# SEM_V1.net
KiCad netlist of a schematic drawn in EAGLE
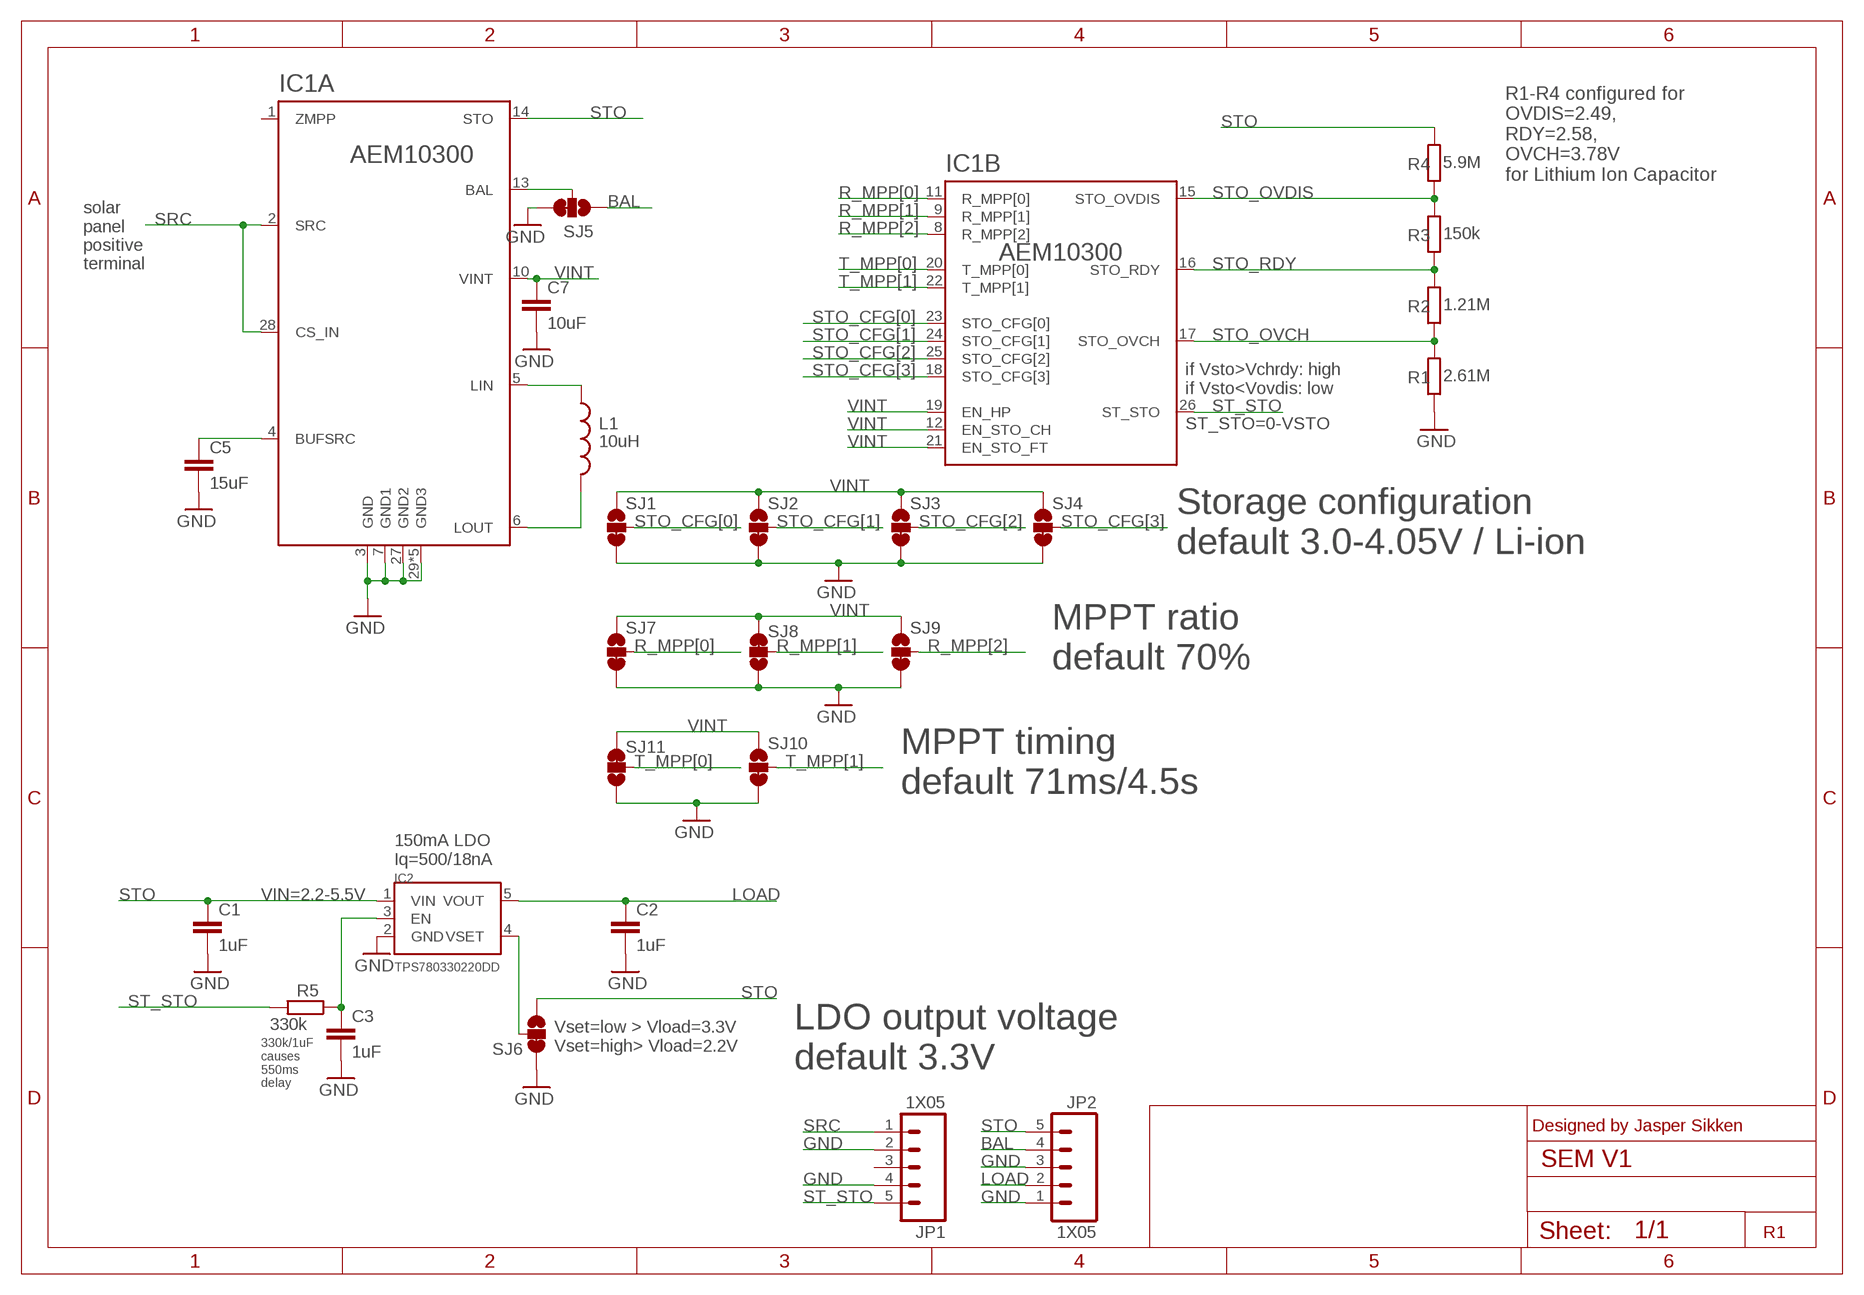
[diagram p0: schematic, sheet 1]

(export (version "E")
  (design (tool "Eeschema 10.0.6"))
  (components
    (comp (ref "C1")
      (value "1uF")
      (footprint "eagle-import:C0402")
      (libsource (lib "eagle-import") (part "C0402_1UF"))
    )
    (comp (ref "C2")
      (value "1uF")
      (footprint "eagle-import:C0402")
      (libsource (lib "eagle-import") (part "C0402_1UF"))
    )
    (comp (ref "C3")
      (value "1uF")
      (footprint "eagle-import:C0402")
      (libsource (lib "eagle-import") (part "C_0402"))
    )
    (comp (ref "C5")
      (value "15uF")
      (footprint "eagle-import:C0402")
      (libsource (lib "eagle-import") (part "C_0402"))
    )
    (comp (ref "C7")
      (value "10uF")
      (footprint "eagle-import:C0402")
      (libsource (lib "eagle-import") (part "C_0402"))
    )
    (comp (ref "IC1")
      (value "AEM10300")
      (footprint "eagle-import:QFN28P4X4")
      (libsource (lib "eagle-import") (part "AEM10300"))
    )
    (comp (ref "IC2")
      (value "TPS780330220DD")
      (footprint "eagle-import:SOT23-5")
      (libsource (lib "eagle-import") (part "TPS780330220DD"))
    )
    (comp (ref "JP1")
      (value "1X05")
      (footprint "eagle-import:1X05_2.54MM_ROUND_NOSILK")
      (libsource (lib "eagle-import") (part "1X05"))
    )
    (comp (ref "JP2")
      (value "1X05")
      (footprint "eagle-import:1X05_2.54MM_ROUND_NOSILK")
      (libsource (lib "eagle-import") (part "1X05"))
    )
    (comp (ref "L1")
      (value "10uH")
      (footprint "eagle-import:L_1008_[2520]")
      (fields (field (name "MF") "MURATA") (field (name "MPN") "DFE252010F-100"))
      (libsource (lib "eagle-import") (part "L"))
    )
    (comp (ref "R1")
      (value "2.61M")
      (footprint "eagle-import:R0402")
      (fields (field (name "MF") "Walsin") (field (name "MPN") "WR04X1004FTL"))
      (libsource (lib "eagle-import") (part "R0402_1M"))
    )
    (comp (ref "R2")
      (value "1.21M")
      (footprint "eagle-import:R0402")
      (fields (field (name "MF") "Walsin") (field (name "MPN") "WR04X1004FTL"))
      (libsource (lib "eagle-import") (part "R0402_1M"))
    )
    (comp (ref "R3")
      (value "150k")
      (footprint "eagle-import:R0402")
      (fields (field (name "MF") "Walsin") (field (name "MPN") "WR04X1004FTL"))
      (libsource (lib "eagle-import") (part "R0402_1M"))
    )
    (comp (ref "R4")
      (value "5.9M")
      (footprint "eagle-import:R0402")
      (fields (field (name "MF") "Walsin") (field (name "MPN") "WR04X1004FTL"))
      (libsource (lib "eagle-import") (part "R0402_1M"))
    )
    (comp (ref "R5")
      (value "330k")
      (footprint "eagle-import:R0402")
      (fields (field (name "MF") "Walsin") (field (name "MPN") "WR04X1004FTL"))
      (libsource (lib "eagle-import") (part "R0402_1M"))
    )
    (comp (ref "SJ1")
      (value "SOLDERJUMPER_3WAY_12SHORT3WAY")
      (footprint "eagle-import:SJ_3S_NC_0402")
      (libsource (lib "eagle-import") (part "SOLDERJUMPER_3WAY_12SHORT3WAY"))
    )
    (comp (ref "SJ2")
      (value "SOLDERJUMPER_3WAY_12SHORT3WAY")
      (footprint "eagle-import:SJ_3S_NC_0402")
      (libsource (lib "eagle-import") (part "SOLDERJUMPER_3WAY_12SHORT3WAY"))
    )
    (comp (ref "SJ3")
      (value "SOLDERJUMPER_3WAY_12SHORT3WAY")
      (footprint "eagle-import:SJ_3S_NC_0402")
      (libsource (lib "eagle-import") (part "SOLDERJUMPER_3WAY_12SHORT3WAY"))
    )
    (comp (ref "SJ4")
      (value "SOLDERJUMPER_3WAY_12SHORT3WAY")
      (footprint "eagle-import:SJ_3S_NC_0402")
      (libsource (lib "eagle-import") (part "SOLDERJUMPER_3WAY_12SHORT3WAY"))
    )
    (comp (ref "SJ5")
      (value "SOLDERJUMPER_3WAY_12SHORT3WAY")
      (footprint "eagle-import:SJ_3S_NC_0402")
      (libsource (lib "eagle-import") (part "SOLDERJUMPER_3WAY_12SHORT3WAY"))
    )
    (comp (ref "SJ6")
      (value "SOLDERJUMPER_3WAY_12SHORT3WAY")
      (footprint "eagle-import:SJ_3S_NC_0402")
      (libsource (lib "eagle-import") (part "SOLDERJUMPER_3WAY_12SHORT3WAY"))
    )
    (comp (ref "SJ7")
      (value "SOLDERJUMPER_3WAY_12SHORT3WAY")
      (footprint "eagle-import:SJ_3S_NC_0402")
      (libsource (lib "eagle-import") (part "SOLDERJUMPER_3WAY_12SHORT3WAY"))
    )
    (comp (ref "SJ8")
      (value "SOLDERJUMPER_3WAY_12SHORT3WAY")
      (footprint "eagle-import:SJ_3S_NC_0402")
      (libsource (lib "eagle-import") (part "SOLDERJUMPER_3WAY_12SHORT3WAY"))
    )
    (comp (ref "SJ9")
      (value "SOLDERJUMPER_3WAY_12SHORT3WAY")
      (footprint "eagle-import:SJ_3S_NC_0402")
      (libsource (lib "eagle-import") (part "SOLDERJUMPER_3WAY_12SHORT3WAY"))
    )
    (comp (ref "SJ10")
      (value "SOLDERJUMPER_3WAY_12SHORT3WAY")
      (footprint "eagle-import:SJ_3S_NC_0402")
      (libsource (lib "eagle-import") (part "SOLDERJUMPER_3WAY_12SHORT3WAY"))
    )
    (comp (ref "SJ11")
      (value "SOLDERJUMPER_3WAY_12SHORT3WAY")
      (footprint "eagle-import:SJ_3S_NC_0402")
      (libsource (lib "eagle-import") (part "SOLDERJUMPER_3WAY_12SHORT3WAY"))
    )
  )
  (nets
    (net (code "1") (name "/BAL") (class "Default")
      (node (ref "JP2") (pin "4") (pinfunction "4_4") (pintype "passive"))
      (node (ref "SJ5") (pin "3") (pinfunction "3_3") (pintype "bidirectional"))
    )
    (net (code "2") (name "/LOAD") (class "Default")
      (node (ref "C2") (pin "1") (pinfunction "1_1") (pintype "passive"))
      (node (ref "IC2") (pin "5") (pinfunction "VOUT_5") (pintype "bidirectional"))
      (node (ref "JP2") (pin "2") (pinfunction "2_2") (pintype "passive"))
    )
    (net (code "3") (name "/R_MPP[0]") (class "Default")
      (node (ref "IC1") (pin "11") (pinfunction "R_MPP[0]_11") (pintype "bidirectional"))
      (node (ref "SJ7") (pin "2") (pinfunction "2_2") (pintype "bidirectional"))
    )
    (net (code "4") (name "/R_MPP[1]") (class "Default")
      (node (ref "IC1") (pin "9") (pinfunction "R_MPP[1]_9") (pintype "bidirectional"))
      (node (ref "SJ8") (pin "2") (pinfunction "2_2") (pintype "bidirectional"))
    )
    (net (code "5") (name "/R_MPP[2]") (class "Default")
      (node (ref "IC1") (pin "8") (pinfunction "R_MPP[2]_8") (pintype "bidirectional"))
      (node (ref "SJ9") (pin "2") (pinfunction "2_2") (pintype "bidirectional"))
    )
    (net (code "6") (name "/SRC") (class "Default")
      (node (ref "IC1") (pin "2") (pinfunction "SRC_2") (pintype "bidirectional"))
      (node (ref "IC1") (pin "28") (pinfunction "CS_IN_28") (pintype "bidirectional"))
      (node (ref "JP1") (pin "1") (pinfunction "1_1") (pintype "passive"))
    )
    (net (code "7") (name "/STO") (class "Default")
      (node (ref "C1") (pin "1") (pinfunction "1_1") (pintype "passive"))
      (node (ref "IC1") (pin "14") (pinfunction "STO_14") (pintype "bidirectional"))
      (node (ref "IC2") (pin "1") (pinfunction "VIN_1") (pintype "bidirectional"))
      (node (ref "JP2") (pin "5") (pinfunction "5_5") (pintype "passive"))
      (node (ref "R4") (pin "2") (pinfunction "2_2") (pintype "passive"))
      (node (ref "SJ6") (pin "3") (pinfunction "3_3") (pintype "bidirectional"))
    )
    (net (code "8") (name "/STO_CFG[0]") (class "Default")
      (node (ref "IC1") (pin "23") (pinfunction "STO_CFG[0]_23") (pintype "bidirectional"))
      (node (ref "SJ1") (pin "2") (pinfunction "2_2") (pintype "bidirectional"))
    )
    (net (code "9") (name "/STO_CFG[1]") (class "Default")
      (node (ref "IC1") (pin "24") (pinfunction "STO_CFG[1]_24") (pintype "bidirectional"))
      (node (ref "SJ2") (pin "2") (pinfunction "2_2") (pintype "bidirectional"))
    )
    (net (code "10") (name "/STO_CFG[2]") (class "Default")
      (node (ref "IC1") (pin "25") (pinfunction "STO_CFG[2]_25") (pintype "bidirectional"))
      (node (ref "SJ3") (pin "2") (pinfunction "2_2") (pintype "bidirectional"))
    )
    (net (code "11") (name "/STO_CFG[3]") (class "Default")
      (node (ref "IC1") (pin "18") (pinfunction "STO_CFG[3]_18") (pintype "bidirectional"))
      (node (ref "SJ4") (pin "2") (pinfunction "2_2") (pintype "bidirectional"))
    )
    (net (code "12") (name "/STO_OVCH") (class "Default")
      (node (ref "IC1") (pin "17") (pinfunction "STO_OVCH_17") (pintype "bidirectional"))
      (node (ref "R1") (pin "2") (pinfunction "2_2") (pintype "passive"))
      (node (ref "R2") (pin "1") (pinfunction "1_1") (pintype "passive"))
    )
    (net (code "13") (name "/STO_OVDIS") (class "Default")
      (node (ref "IC1") (pin "15") (pinfunction "STO_OVDIS_15") (pintype "bidirectional"))
      (node (ref "R3") (pin "2") (pinfunction "2_2") (pintype "passive"))
      (node (ref "R4") (pin "1") (pinfunction "1_1") (pintype "passive"))
    )
    (net (code "14") (name "/STO_RDY") (class "Default")
      (node (ref "IC1") (pin "16") (pinfunction "STO_RDY_16") (pintype "bidirectional"))
      (node (ref "R2") (pin "2") (pinfunction "2_2") (pintype "passive"))
      (node (ref "R3") (pin "1") (pinfunction "1_1") (pintype "passive"))
    )
    (net (code "15") (name "/ST_STO") (class "Default")
      (node (ref "IC1") (pin "26") (pinfunction "ST_STO_26") (pintype "bidirectional"))
      (node (ref "JP1") (pin "5") (pinfunction "5_5") (pintype "passive"))
      (node (ref "R5") (pin "2") (pinfunction "2_2") (pintype "passive"))
    )
    (net (code "16") (name "/T_MPP[0]") (class "Default")
      (node (ref "IC1") (pin "20") (pinfunction "T_MPP[0]_20") (pintype "bidirectional"))
      (node (ref "SJ11") (pin "2") (pinfunction "2_2") (pintype "bidirectional"))
    )
    (net (code "17") (name "/T_MPP[1]") (class "Default")
      (node (ref "IC1") (pin "22") (pinfunction "T_MPP[1]_22") (pintype "bidirectional"))
      (node (ref "SJ10") (pin "2") (pinfunction "2_2") (pintype "bidirectional"))
    )
    (net (code "18") (name "/VINT") (class "Default")
      (node (ref "C7") (pin "1") (pinfunction "1_1") (pintype "passive"))
      (node (ref "IC1") (pin "10") (pinfunction "VINT_10") (pintype "bidirectional"))
      (node (ref "IC1") (pin "12") (pinfunction "EN_STO_CH_12") (pintype "bidirectional"))
      (node (ref "IC1") (pin "19") (pinfunction "EN_HP_19") (pintype "bidirectional"))
      (node (ref "IC1") (pin "21") (pinfunction "EN_STO_FT_21") (pintype "bidirectional"))
      (node (ref "SJ1") (pin "3") (pinfunction "3_3") (pintype "bidirectional"))
      (node (ref "SJ10") (pin "3") (pinfunction "3_3") (pintype "bidirectional"))
      (node (ref "SJ11") (pin "1") (pinfunction "1_1") (pintype "bidirectional"))
      (node (ref "SJ2") (pin "3") (pinfunction "3_3") (pintype "bidirectional"))
      (node (ref "SJ3") (pin "3") (pinfunction "3_3") (pintype "bidirectional"))
      (node (ref "SJ4") (pin "3") (pinfunction "3_3") (pintype "bidirectional"))
      (node (ref "SJ7") (pin "3") (pinfunction "3_3") (pintype "bidirectional"))
      (node (ref "SJ8") (pin "1") (pinfunction "1_1") (pintype "bidirectional"))
      (node (ref "SJ9") (pin "3") (pinfunction "3_3") (pintype "bidirectional"))
    )
    (net (code "19") (name "GND") (class "Default")
      (node (ref "C1") (pin "2") (pinfunction "2_2") (pintype "passive"))
      (node (ref "C2") (pin "2") (pinfunction "2_2") (pintype "passive"))
      (node (ref "C3") (pin "2") (pinfunction "2_2") (pintype "passive"))
      (node (ref "C5") (pin "2") (pinfunction "2_2") (pintype "passive"))
      (node (ref "C7") (pin "2") (pinfunction "2_2") (pintype "passive"))
      (node (ref "IC1") (pin "27") (pinfunction "GND2_27") (pintype "bidirectional"))
      (node (ref "IC1") (pin "29") (pinfunction "GND3_29") (pintype "bidirectional"))
      (node (ref "IC1") (pin "3") (pinfunction "GND_3") (pintype "bidirectional"))
      (node (ref "IC1") (pin "7") (pinfunction "GND1_7") (pintype "bidirectional"))
      (node (ref "IC1") (pin "P$1") (pinfunction "GND3_P$1") (pintype "bidirectional"))
      (node (ref "IC1") (pin "P$2") (pinfunction "GND3_P$2") (pintype "bidirectional"))
      (node (ref "IC1") (pin "P$3") (pinfunction "GND3_P$3") (pintype "bidirectional"))
      (node (ref "IC1") (pin "P$4") (pinfunction "GND3_P$4") (pintype "bidirectional"))
      (node (ref "IC2") (pin "2") (pinfunction "GND_2") (pintype "bidirectional"))
      (node (ref "JP1") (pin "2") (pinfunction "2_2") (pintype "passive"))
      (node (ref "JP1") (pin "4") (pinfunction "4_4") (pintype "passive"))
      (node (ref "JP2") (pin "1") (pinfunction "1_1") (pintype "passive"))
      (node (ref "JP2") (pin "3") (pinfunction "3_3") (pintype "passive"))
      (node (ref "R1") (pin "1") (pinfunction "1_1") (pintype "passive"))
      (node (ref "SJ1") (pin "1") (pinfunction "1_1") (pintype "bidirectional"))
      (node (ref "SJ10") (pin "1") (pinfunction "1_1") (pintype "bidirectional"))
      (node (ref "SJ11") (pin "3") (pinfunction "3_3") (pintype "bidirectional"))
      (node (ref "SJ2") (pin "1") (pinfunction "1_1") (pintype "bidirectional"))
      (node (ref "SJ3") (pin "1") (pinfunction "1_1") (pintype "bidirectional"))
      (node (ref "SJ4") (pin "1") (pinfunction "1_1") (pintype "bidirectional"))
      (node (ref "SJ5") (pin "1") (pinfunction "1_1") (pintype "bidirectional"))
      (node (ref "SJ6") (pin "1") (pinfunction "1_1") (pintype "bidirectional"))
      (node (ref "SJ7") (pin "1") (pinfunction "1_1") (pintype "bidirectional"))
      (node (ref "SJ8") (pin "3") (pinfunction "3_3") (pintype "bidirectional"))
      (node (ref "SJ9") (pin "1") (pinfunction "1_1") (pintype "bidirectional"))
    )
    (net (code "20") (name "Net-(IC1A-BAL)") (class "Default")
      (node (ref "IC1") (pin "13") (pinfunction "BAL_13") (pintype "bidirectional"))
      (node (ref "SJ5") (pin "2") (pinfunction "2_2") (pintype "bidirectional"))
    )
    (net (code "21") (name "Net-(IC1A-BUFSRC)") (class "Default")
      (node (ref "C5") (pin "1") (pinfunction "1_1") (pintype "passive"))
      (node (ref "IC1") (pin "4") (pinfunction "BUFSRC_4") (pintype "bidirectional"))
    )
    (net (code "22") (name "Net-(IC1A-LIN)") (class "Default")
      (node (ref "IC1") (pin "5") (pinfunction "LIN_5") (pintype "bidirectional"))
      (node (ref "L1") (pin "1") (pinfunction "1_1") (pintype "passive"))
    )
    (net (code "23") (name "Net-(IC1A-LOUT)") (class "Default")
      (node (ref "IC1") (pin "6") (pinfunction "LOUT_6") (pintype "bidirectional"))
      (node (ref "L1") (pin "2") (pinfunction "2_2") (pintype "passive"))
    )
    (net (code "24") (name "Net-(IC2-EN)") (class "Default")
      (node (ref "C3") (pin "1") (pinfunction "1_1") (pintype "passive"))
      (node (ref "IC2") (pin "3") (pinfunction "EN_3") (pintype "bidirectional"))
      (node (ref "R5") (pin "1") (pinfunction "1_1") (pintype "passive"))
    )
    (net (code "25") (name "Net-(IC2-VSET)") (class "Default")
      (node (ref "IC2") (pin "4") (pinfunction "VSET_4") (pintype "bidirectional"))
      (node (ref "SJ6") (pin "2") (pinfunction "2_2") (pintype "bidirectional"))
    )
    (net (code "26") (name "unconnected-(IC1A-ZMPP-Pad1)") (class "Default")
      (node (ref "IC1") (pin "1") (pinfunction "ZMPP_1") (pintype "bidirectional"))
    )
    (net (code "27") (name "unconnected-(JP1-Pad3)") (class "Default")
      (node (ref "JP1") (pin "3") (pinfunction "3_3") (pintype "passive"))
    )
  )
)
